# door.net
KiCad netlist of a schematic drawn in EAGLE
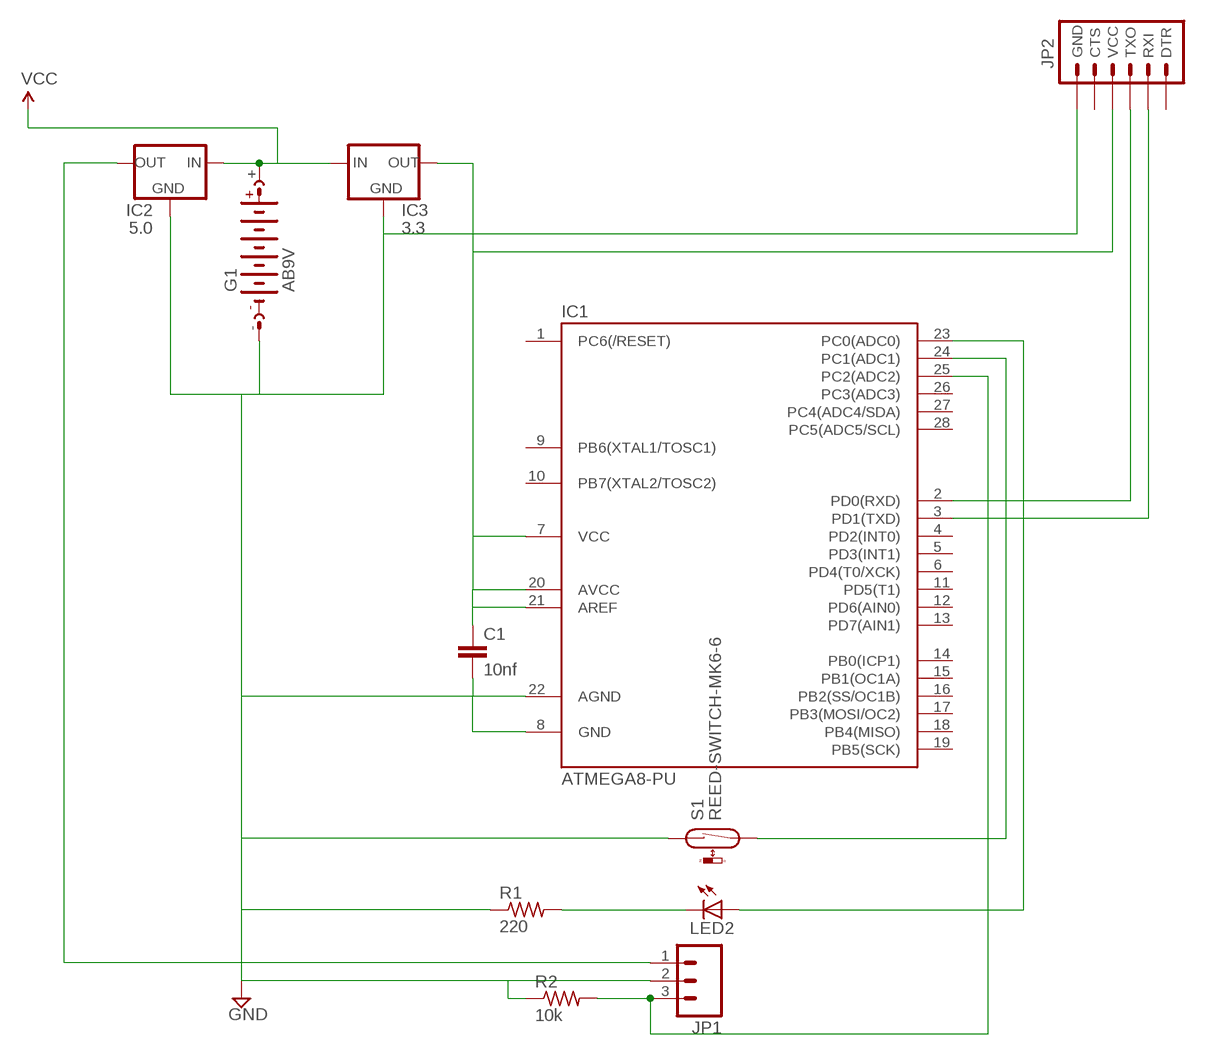
[diagram p0: schematic, sheet 1]

(export (version "E")
  (design (tool "Eeschema 10.0.6"))
  (components
    (comp (ref "C1")
      (value "10nf")
      (footprint "eagle-import:C2.5-4")
      (libsource (lib "eagle-import") (part "C2.5/4"))
    )
    (comp (ref "G1")
      (value "AB9V")
      (footprint "eagle-import:AB9V")
      (libsource (lib "eagle-import") (part "AB9V"))
    )
    (comp (ref "IC1")
      (value "ATMEGA8-PU")
      (footprint "eagle-import:DIL28-3")
      (libsource (lib "eagle-import") (part "ATMEGA8-PU"))
    )
    (comp (ref "IC2")
      (value "5.0")
      (footprint "eagle-import:TO220-IGO")
      (libsource (lib "eagle-import") (part "V_REG_78XXSINK"))
    )
    (comp (ref "IC3")
      (value "3.3")
      (footprint "eagle-import:TO220-IGO")
      (libsource (lib "eagle-import") (part "V_REG_78XXSINK"))
    )
    (comp (ref "JP1")
      (value "M03PTH")
      (footprint "eagle-import:1X03")
      (libsource (lib "eagle-import") (part "M03PTH"))
    )
    (comp (ref "JP2")
      (value "ARDUINO_SERIAL_PROGRAMLONGPADS")
      (footprint "eagle-import:1X06_LONGPADS")
      (libsource (lib "eagle-import") (part "ARDUINO_SERIAL_PROGRAMLONGPADS"))
    )
    (comp (ref "LED2")
      (value "LED3MM")
      (footprint "eagle-import:LED3MM")
      (libsource (lib "eagle-import") (part "LED3MM"))
    )
    (comp (ref "R1")
      (value "220")
      (footprint "eagle-import:0207_12")
      (libsource (lib "eagle-import") (part "R-US_0207/12"))
    )
    (comp (ref "R2")
      (value "10k")
      (footprint "eagle-import:0207_12")
      (libsource (lib "eagle-import") (part "R-US_0207/12"))
    )
    (comp (ref "S1")
      (value "REED-SWITCH-MK6-6")
      (footprint "eagle-import:MK6-6")
      (libsource (lib "eagle-import") (part "REED-SWITCH-MK6-6"))
    )
  )
  (nets
    (net (code "1") (name "GND") (class "Default")
      (node (ref "C1") (pin "2") (pinfunction "2_2") (pintype "passive"))
      (node (ref "G1") (pin "-") (pinfunction "-_-") (pintype "passive"))
      (node (ref "IC1") (pin "22") (pinfunction "AGND_22") (pintype "power_in"))
      (node (ref "IC1") (pin "8") (pinfunction "GND_8") (pintype "power_in"))
      (node (ref "IC2") (pin "GND") (pinfunction "GND_GND") (pintype "input"))
      (node (ref "IC3") (pin "GND") (pinfunction "GND_GND") (pintype "input"))
      (node (ref "JP1") (pin "2") (pinfunction "GND_2") (pintype "passive"))
      (node (ref "JP2") (pin "6") (pinfunction "GND_6") (pintype "passive"))
      (node (ref "R1") (pin "1") (pinfunction "1_1") (pintype "passive"))
      (node (ref "R2") (pin "1") (pinfunction "1_1") (pintype "passive"))
      (node (ref "S1") (pin "1") (pinfunction "1_1") (pintype "passive"))
    )
    (net (code "2") (name "Net-(IC1-AREF)") (class "Default")
      (node (ref "C1") (pin "1") (pinfunction "1_1") (pintype "passive"))
      (node (ref "IC1") (pin "20") (pinfunction "AVCC_20") (pintype "passive"))
      (node (ref "IC1") (pin "21") (pinfunction "AREF_21") (pintype "passive"))
      (node (ref "IC1") (pin "7") (pinfunction "VCC_7") (pintype "power_in"))
      (node (ref "IC3") (pin "OUT") (pinfunction "OUT_OUT") (pintype "output"))
      (node (ref "JP2") (pin "4") (pinfunction "VCC_4") (pintype "passive"))
    )
    (net (code "3") (name "Net-(IC1-PC0(ADC0))") (class "Default")
      (node (ref "IC1") (pin "23") (pinfunction "PC0(ADC0)_23") (pintype "bidirectional"))
      (node (ref "LED2") (pin "A") (pinfunction "A_A") (pintype "passive"))
    )
    (net (code "4") (name "Net-(IC1-PC1(ADC1))") (class "Default")
      (node (ref "IC1") (pin "24") (pinfunction "PC1(ADC1)_24") (pintype "bidirectional"))
      (node (ref "S1") (pin "2") (pinfunction "2_2") (pintype "passive"))
    )
    (net (code "5") (name "Net-(IC1-PC2(ADC2))") (class "Default")
      (node (ref "IC1") (pin "25") (pinfunction "PC2(ADC2)_25") (pintype "bidirectional"))
      (node (ref "JP1") (pin "3") (pinfunction "VCC_3") (pintype "passive"))
      (node (ref "R2") (pin "2") (pinfunction "2_2") (pintype "passive"))
    )
    (net (code "6") (name "Net-(IC1-PD0(RXD))") (class "Default")
      (node (ref "IC1") (pin "2") (pinfunction "PD0(RXD)_2") (pintype "bidirectional"))
      (node (ref "JP2") (pin "3") (pinfunction "TXO_3") (pintype "passive"))
    )
    (net (code "7") (name "Net-(IC1-PD1(TXD))") (class "Default")
      (node (ref "IC1") (pin "3") (pinfunction "PD1(TXD)_3") (pintype "bidirectional"))
      (node (ref "JP2") (pin "2") (pinfunction "RXI_2") (pintype "passive"))
    )
    (net (code "8") (name "Net-(JP1-OUT)") (class "Default")
      (node (ref "IC2") (pin "OUT") (pinfunction "OUT_OUT") (pintype "output"))
      (node (ref "JP1") (pin "1") (pinfunction "OUT_1") (pintype "passive"))
    )
    (net (code "9") (name "Net-(LED2-C)") (class "Default")
      (node (ref "LED2") (pin "K") (pinfunction "C_K") (pintype "passive"))
      (node (ref "R1") (pin "2") (pinfunction "2_2") (pintype "passive"))
    )
    (net (code "10") (name "VCC") (class "Default")
      (node (ref "G1") (pin "+") (pinfunction "+_+") (pintype "passive"))
      (node (ref "IC2") (pin "IN") (pinfunction "IN_IN") (pintype "input"))
      (node (ref "IC3") (pin "IN") (pinfunction "IN_IN") (pintype "input"))
    )
    (net (code "11") (name "unconnected-(IC1-PB0(ICP1)-Pad14)") (class "Default")
      (node (ref "IC1") (pin "14") (pinfunction "PB0(ICP1)_14") (pintype "bidirectional"))
    )
    (net (code "12") (name "unconnected-(IC1-PB1(OC1A)-Pad15)") (class "Default")
      (node (ref "IC1") (pin "15") (pinfunction "PB1(OC1A)_15") (pintype "bidirectional"))
    )
    (net (code "13") (name "unconnected-(IC1-PB2(SS{slash}OC1B)-Pad16)") (class "Default")
      (node (ref "IC1") (pin "16") (pinfunction "PB2(SS/OC1B)_16") (pintype "bidirectional"))
    )
    (net (code "14") (name "unconnected-(IC1-PB3(MOSI{slash}OC2)-Pad17)") (class "Default")
      (node (ref "IC1") (pin "17") (pinfunction "PB3(MOSI/OC2)_17") (pintype "bidirectional"))
    )
    (net (code "15") (name "unconnected-(IC1-PB4(MISO)-Pad18)") (class "Default")
      (node (ref "IC1") (pin "18") (pinfunction "PB4(MISO)_18") (pintype "bidirectional"))
    )
    (net (code "16") (name "unconnected-(IC1-PB5(SCK)-Pad19)") (class "Default")
      (node (ref "IC1") (pin "19") (pinfunction "PB5(SCK)_19") (pintype "bidirectional"))
    )
    (net (code "17") (name "unconnected-(IC1-PB6(XTAL1{slash}TOSC1)-Pad9)") (class "Default")
      (node (ref "IC1") (pin "9") (pinfunction "PB6(XTAL1/TOSC1)_9") (pintype "bidirectional"))
    )
    (net (code "18") (name "unconnected-(IC1-PB7(XTAL2{slash}TOSC2)-Pad10)") (class "Default")
      (node (ref "IC1") (pin "10") (pinfunction "PB7(XTAL2/TOSC2)_10") (pintype "bidirectional"))
    )
    (net (code "19") (name "unconnected-(IC1-PC3(ADC3)-Pad26)") (class "Default")
      (node (ref "IC1") (pin "26") (pinfunction "PC3(ADC3)_26") (pintype "bidirectional"))
    )
    (net (code "20") (name "unconnected-(IC1-PC4(ADC4{slash}SDA)-Pad27)") (class "Default")
      (node (ref "IC1") (pin "27") (pinfunction "PC4(ADC4/SDA)_27") (pintype "bidirectional"))
    )
    (net (code "21") (name "unconnected-(IC1-PC5(ADC5{slash}SCL)-Pad28)") (class "Default")
      (node (ref "IC1") (pin "28") (pinfunction "PC5(ADC5/SCL)_28") (pintype "bidirectional"))
    )
    (net (code "22") (name "unconnected-(IC1-PC6({slash}RESET)-Pad1)") (class "Default")
      (node (ref "IC1") (pin "1") (pinfunction "PC6(/RESET)_1") (pintype "bidirectional"))
    )
    (net (code "23") (name "unconnected-(IC1-PD2(INT0)-Pad4)") (class "Default")
      (node (ref "IC1") (pin "4") (pinfunction "PD2(INT0)_4") (pintype "bidirectional"))
    )
    (net (code "24") (name "unconnected-(IC1-PD3(INT1)-Pad5)") (class "Default")
      (node (ref "IC1") (pin "5") (pinfunction "PD3(INT1)_5") (pintype "bidirectional"))
    )
    (net (code "25") (name "unconnected-(IC1-PD4(T0{slash}XCK)-Pad6)") (class "Default")
      (node (ref "IC1") (pin "6") (pinfunction "PD4(T0/XCK)_6") (pintype "bidirectional"))
    )
    (net (code "26") (name "unconnected-(IC1-PD5(T1)-Pad11)") (class "Default")
      (node (ref "IC1") (pin "11") (pinfunction "PD5(T1)_11") (pintype "bidirectional"))
    )
    (net (code "27") (name "unconnected-(IC1-PD6(AIN0)-Pad12)") (class "Default")
      (node (ref "IC1") (pin "12") (pinfunction "PD6(AIN0)_12") (pintype "bidirectional"))
    )
    (net (code "28") (name "unconnected-(IC1-PD7(AIN1)-Pad13)") (class "Default")
      (node (ref "IC1") (pin "13") (pinfunction "PD7(AIN1)_13") (pintype "bidirectional"))
    )
    (net (code "29") (name "unconnected-(JP2-CTS-Pad5)") (class "Default")
      (node (ref "JP2") (pin "5") (pinfunction "CTS_5") (pintype "passive"))
    )
    (net (code "30") (name "unconnected-(JP2-DTR-Pad1)") (class "Default")
      (node (ref "JP2") (pin "1") (pinfunction "DTR_1") (pintype "passive"))
    )
  )
)
